# ProPrj_RP2040_SERVO_BOARD_2026-06-01.net
KiCad netlist of a schematic drawn in EasyEDA Pro
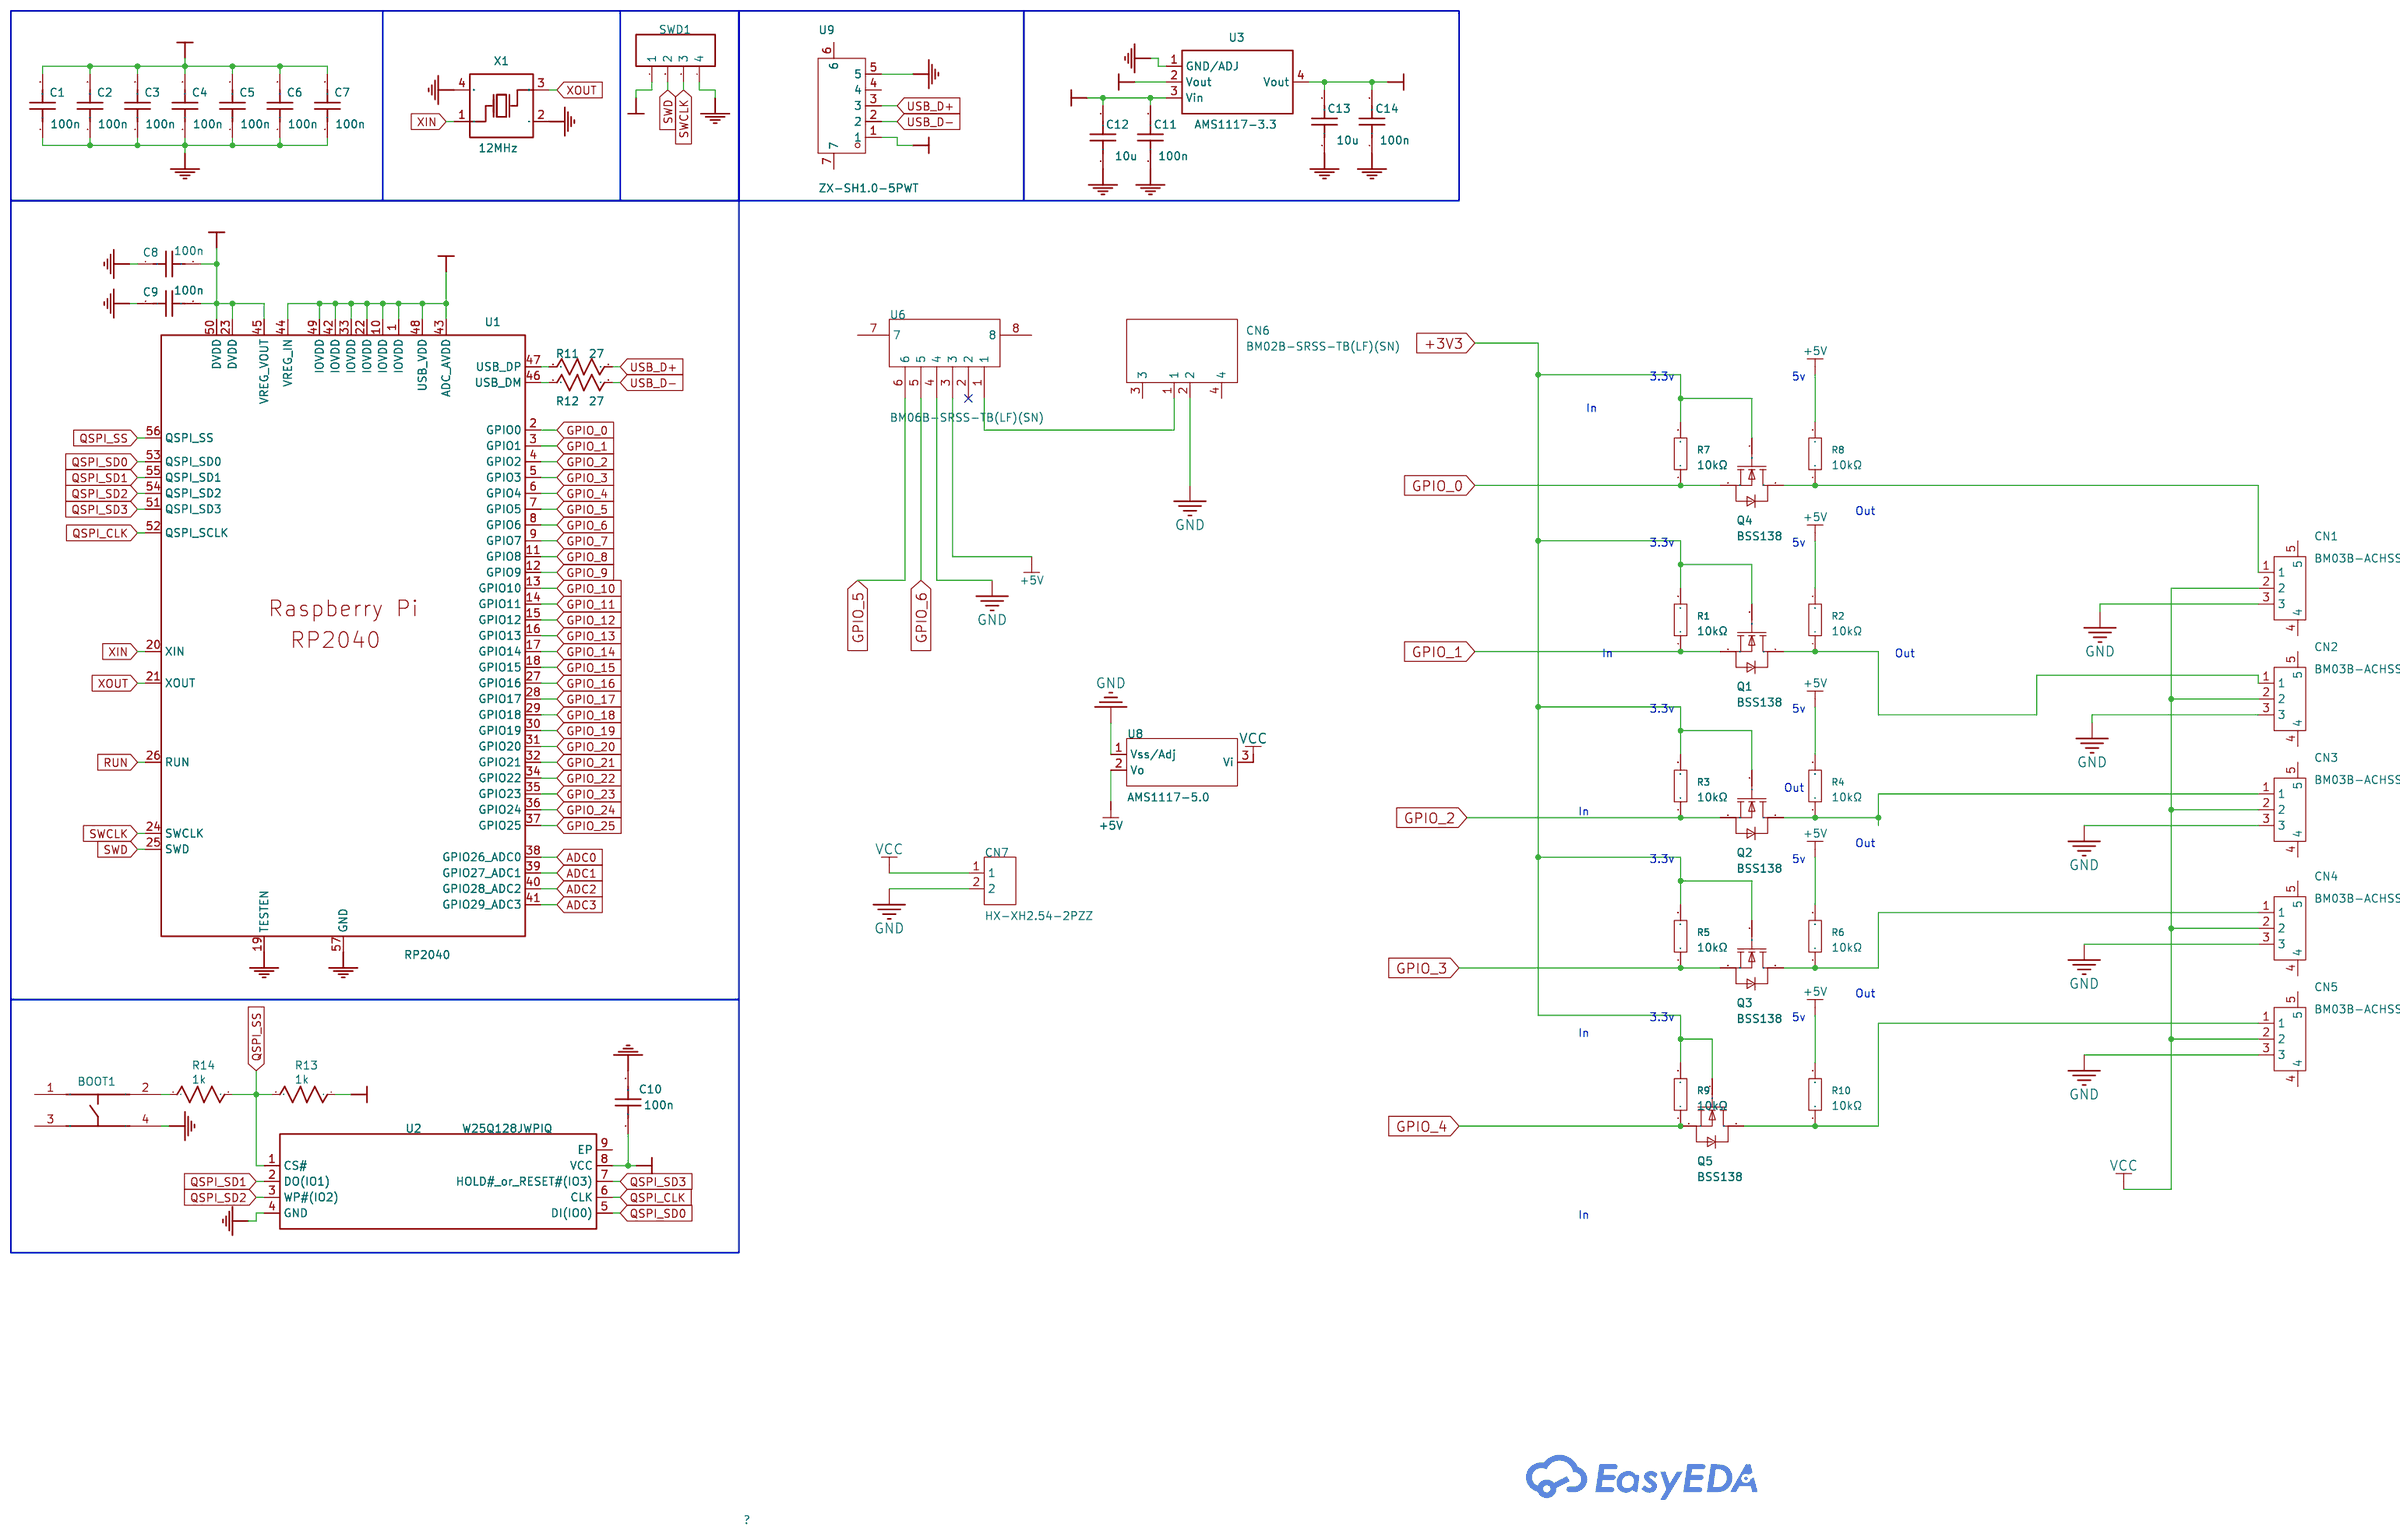
[diagram p0: schematic sheet]

(export (version "E")
  (design (tool "Eeschema 10.0.6"))
  (components
    (comp (ref "BOOT1")
      (value "PTS810SJM250SMTRLFS")
      (footprint "easyedapro:KEY-SMD_4P-L4.2-W3.2-P2.20-LS4.6")
      (fields (field (name "Manufacturer") "C&K") (field (name "Contributor") "LCSC"))
      (libsource (lib "easyedapro") (part "PTS810SJM250SMTRLFS"))
    )
    (comp (ref "C1")
      (value "100n")
      (footprint "easyedapro:C0603")
      (fields (field (name "Contributor") "LCEDA_Lib"))
      (libsource (lib "easyedapro") (part "100n"))
    )
    (comp (ref "C2")
      (value "100n")
      (footprint "easyedapro:C0603")
      (fields (field (name "Contributor") "LCEDA_Lib"))
      (libsource (lib "easyedapro") (part "100n"))
    )
    (comp (ref "C3")
      (value "100n")
      (footprint "easyedapro:C0603")
      (fields (field (name "Contributor") "LCEDA_Lib"))
      (libsource (lib "easyedapro") (part "100n"))
    )
    (comp (ref "C4")
      (value "100n")
      (footprint "easyedapro:C0603")
      (fields (field (name "Contributor") "LCEDA_Lib"))
      (libsource (lib "easyedapro") (part "100n"))
    )
    (comp (ref "C5")
      (value "100n")
      (footprint "easyedapro:C0603")
      (fields (field (name "Contributor") "LCEDA_Lib"))
      (libsource (lib "easyedapro") (part "100n"))
    )
    (comp (ref "C6")
      (value "100n")
      (footprint "easyedapro:C0603")
      (fields (field (name "Contributor") "LCEDA_Lib"))
      (libsource (lib "easyedapro") (part "100n"))
    )
    (comp (ref "C7")
      (value "100n")
      (footprint "easyedapro:C0603")
      (fields (field (name "Contributor") "LCEDA_Lib"))
      (libsource (lib "easyedapro") (part "100n"))
    )
    (comp (ref "C8")
      (value "100n")
      (footprint "easyedapro:C0603")
      (fields (field (name "Contributor") "LCEDA_Lib"))
      (libsource (lib "easyedapro") (part "100n"))
    )
    (comp (ref "C9")
      (value "100n")
      (footprint "easyedapro:C0603")
      (fields (field (name "Contributor") "LCEDA_Lib"))
      (libsource (lib "easyedapro") (part "100n"))
    )
    (comp (ref "C10")
      (value "100n")
      (footprint "easyedapro:C0603")
      (fields (field (name "Contributor") "LCEDA_Lib"))
      (libsource (lib "easyedapro") (part "100n"))
    )
    (comp (ref "C11")
      (value "100n")
      (footprint "easyedapro:C0603")
      (fields (field (name "Contributor") "LCEDA_Lib"))
      (libsource (lib "easyedapro") (part "100n"))
    )
    (comp (ref "C12")
      (value "10u")
      (footprint "easyedapro:C0603")
      (fields (field (name "Contributor") "LCEDA_Lib"))
      (libsource (lib "easyedapro") (part "10u"))
    )
    (comp (ref "C13")
      (value "10u")
      (footprint "easyedapro:C0603")
      (fields (field (name "Contributor") "LCEDA_Lib"))
      (libsource (lib "easyedapro") (part "10u"))
    )
    (comp (ref "C14")
      (value "100n")
      (footprint "easyedapro:C0603")
      (fields (field (name "Contributor") "LCEDA_Lib"))
      (libsource (lib "easyedapro") (part "100n"))
    )
    (comp (ref "CN1")
      (value "BM03B-ACHSS-GAN-TF(LF)(SN)")
      (footprint "easyedapro:CONN-SMD_3P-P1.20_BM03B-ACHSS-GAN-TF")
      (fields (field (name "Manufacturer") "JST"))
      (libsource (lib "easyedapro") (part "BM03B-ACHSS-GAN-TF(LF)(SN)"))
    )
    (comp (ref "CN2")
      (value "BM03B-ACHSS-GAN-TF(LF)(SN)")
      (footprint "easyedapro:CONN-SMD_3P-P1.20_BM03B-ACHSS-GAN-TF")
      (fields (field (name "Manufacturer") "JST"))
      (libsource (lib "easyedapro") (part "BM03B-ACHSS-GAN-TF(LF)(SN)"))
    )
    (comp (ref "CN3")
      (value "BM03B-ACHSS-GAN-TF(LF)(SN)")
      (footprint "easyedapro:CONN-SMD_3P-P1.20_BM03B-ACHSS-GAN-TF")
      (fields (field (name "Manufacturer") "JST"))
      (libsource (lib "easyedapro") (part "BM03B-ACHSS-GAN-TF(LF)(SN)"))
    )
    (comp (ref "CN4")
      (value "BM03B-ACHSS-GAN-TF(LF)(SN)")
      (footprint "easyedapro:CONN-SMD_3P-P1.20_BM03B-ACHSS-GAN-TF")
      (fields (field (name "Manufacturer") "JST"))
      (libsource (lib "easyedapro") (part "BM03B-ACHSS-GAN-TF(LF)(SN)"))
    )
    (comp (ref "CN5")
      (value "BM03B-ACHSS-GAN-TF(LF)(SN)")
      (footprint "easyedapro:CONN-SMD_3P-P1.20_BM03B-ACHSS-GAN-TF")
      (fields (field (name "Manufacturer") "JST"))
      (libsource (lib "easyedapro") (part "BM03B-ACHSS-GAN-TF(LF)(SN)"))
    )
    (comp (ref "CN6")
      (value "BM02B-SRSS-TB(LF)(SN)")
      (footprint "easyedapro:CONN-TH_BM02B-SRSS-TB-LF-SN")
      (fields (field (name "Manufacturer") "JST"))
      (libsource (lib "easyedapro") (part "BM02B-SRSS-TB (LF)(SN)"))
    )
    (comp (ref "CN7")
      (value "HX-XH2.54-2PZZ")
      (footprint "easyedapro:CONN-TH_2P-P2.50_HX-2.54MM-2P-ZZ-MS")
      (fields (field (name "Manufacturer") "hanxia(韩下)"))
      (libsource (lib "easyedapro") (part "HX-XH2.54-2PZZ"))
    )
    (comp (ref "Q1")
      (value "BSS138")
      (footprint "easyedapro:SOT-23-3_L3.0-W1.7-P0.95-LS2.9-BR")
      (fields (field (name "Manufacturer") "luJing(鲁晶)"))
      (libsource (lib "easyedapro") (part "BSS138_C53058666"))
    )
    (comp (ref "Q2")
      (value "BSS138")
      (footprint "easyedapro:SOT-23-3_L3.0-W1.7-P0.95-LS2.9-BR")
      (fields (field (name "Manufacturer") "luJing(鲁晶)"))
      (libsource (lib "easyedapro") (part "BSS138_C53058666"))
    )
    (comp (ref "Q3")
      (value "BSS138")
      (footprint "easyedapro:SOT-23-3_L3.0-W1.7-P0.95-LS2.9-BR")
      (fields (field (name "Manufacturer") "luJing(鲁晶)"))
      (libsource (lib "easyedapro") (part "BSS138_C53058666"))
    )
    (comp (ref "Q4")
      (value "BSS138")
      (footprint "easyedapro:SOT-23-3_L3.0-W1.7-P0.95-LS2.9-BR")
      (fields (field (name "Manufacturer") "luJing(鲁晶)"))
      (libsource (lib "easyedapro") (part "BSS138_C53058666"))
    )
    (comp (ref "Q5")
      (value "BSS138")
      (footprint "easyedapro:SOT-23-3_L3.0-W1.7-P0.95-LS2.9-BR")
      (fields (field (name "Manufacturer") "luJing(鲁晶)"))
      (libsource (lib "easyedapro") (part "BSS138_C53058666"))
    )
    (comp (ref "R1")
      (value "10kΩ")
      (footprint "easyedapro:R0402")
      (fields
        (field (name "Manufacturer Part") "TR0402D10K0Q1025Z")
        (field (name "Manufacturer") "EVER OHMS(天二科技)")
      )
      (libsource (lib "easyedapro") (part "TR0402D10KQ1025"))
    )
    (comp (ref "R2")
      (value "10kΩ")
      (footprint "easyedapro:R0402")
      (fields
        (field (name "Manufacturer Part") "TR0402D10K0Q1025Z")
        (field (name "Manufacturer") "EVER OHMS(天二科技)")
      )
      (libsource (lib "easyedapro") (part "TR0402D10KQ1025"))
    )
    (comp (ref "R3")
      (value "10kΩ")
      (footprint "easyedapro:R0402")
      (fields
        (field (name "Manufacturer Part") "TR0402D10K0Q1025Z")
        (field (name "Manufacturer") "EVER OHMS(天二科技)")
      )
      (libsource (lib "easyedapro") (part "TR0402D10KQ1025"))
    )
    (comp (ref "R4")
      (value "10kΩ")
      (footprint "easyedapro:R0402")
      (fields
        (field (name "Manufacturer Part") "TR0402D10K0Q1025Z")
        (field (name "Manufacturer") "EVER OHMS(天二科技)")
      )
      (libsource (lib "easyedapro") (part "TR0402D10KQ1025"))
    )
    (comp (ref "R5")
      (value "10kΩ")
      (footprint "easyedapro:R0402")
      (fields
        (field (name "Manufacturer Part") "TR0402D10K0Q1025Z")
        (field (name "Manufacturer") "EVER OHMS(天二科技)")
      )
      (libsource (lib "easyedapro") (part "TR0402D10KQ1025"))
    )
    (comp (ref "R6")
      (value "10kΩ")
      (footprint "easyedapro:R0402")
      (fields
        (field (name "Manufacturer Part") "TR0402D10K0Q1025Z")
        (field (name "Manufacturer") "EVER OHMS(天二科技)")
      )
      (libsource (lib "easyedapro") (part "TR0402D10KQ1025"))
    )
    (comp (ref "R7")
      (value "10kΩ")
      (footprint "easyedapro:R0402")
      (fields
        (field (name "Manufacturer Part") "TR0402D10K0Q1025Z")
        (field (name "Manufacturer") "EVER OHMS(天二科技)")
      )
      (libsource (lib "easyedapro") (part "TR0402D10KQ1025"))
    )
    (comp (ref "R8")
      (value "10kΩ")
      (footprint "easyedapro:R0402")
      (fields
        (field (name "Manufacturer Part") "TR0402D10K0Q1025Z")
        (field (name "Manufacturer") "EVER OHMS(天二科技)")
      )
      (libsource (lib "easyedapro") (part "TR0402D10KQ1025"))
    )
    (comp (ref "R9")
      (value "10kΩ")
      (footprint "easyedapro:R0402")
      (fields
        (field (name "Manufacturer Part") "TR0402D10K0Q1025Z")
        (field (name "Manufacturer") "EVER OHMS(天二科技)")
      )
      (libsource (lib "easyedapro") (part "TR0402D10KQ1025"))
    )
    (comp (ref "R10")
      (value "10kΩ")
      (footprint "easyedapro:R0402")
      (fields
        (field (name "Manufacturer Part") "TR0402D10K0Q1025Z")
        (field (name "Manufacturer") "EVER OHMS(天二科技)")
      )
      (libsource (lib "easyedapro") (part "TR0402D10KQ1025"))
    )
    (comp (ref "R11")
      (value "27")
      (footprint "easyedapro:R0603")
      (fields (field (name "Contributor") "LCEDA_Lib"))
      (libsource (lib "easyedapro") (part "27"))
    )
    (comp (ref "R12")
      (value "27")
      (footprint "easyedapro:R0603")
      (fields (field (name "Contributor") "LCEDA_Lib"))
      (libsource (lib "easyedapro") (part "27"))
    )
    (comp (ref "R13")
      (value "1k")
      (footprint "easyedapro:R0603")
      (fields (field (name "Contributor") "LCEDA_Lib"))
      (libsource (lib "easyedapro") (part "1k"))
    )
    (comp (ref "R14")
      (value "1k")
      (footprint "easyedapro:R0603")
      (fields (field (name "Contributor") "LCEDA_Lib"))
      (libsource (lib "easyedapro") (part "1k"))
    )
    (comp (ref "SWD1")
      (value "HDR-M-2.54_1x4")
      (footprint "easyedapro:HDR-M-2.54_1X4")
      (fields (field (name "Contributor") "LCEDA_Lib"))
      (libsource (lib "easyedapro") (part "HDR-M-2.54_1x4"))
    )
    (comp (ref "U1")
      (value "RP2040")
      (footprint "easyedapro:LQFN-56_L7.0-W7.0-P0.4-EP")
      (fields (field (name "Manufacturer") "Raspberry Pi(树莓派)") (field (name "Contributor") "LCSC"))
      (libsource (lib "easyedapro") (part "RP2040"))
    )
    (comp (ref "U2")
      (value "W25Q128JWPIQ")
      (footprint "easyedapro:WSON-8_L6.0-W5.0-P1.27-BL-EP")
      (fields (field (name "Manufacturer") "WINBOND(华邦)") (field (name "Contributor") "LCSC"))
      (libsource (lib "easyedapro") (part "W25Q128JWPIQ"))
    )
    (comp (ref "U3")
      (value "AMS1117-3.3")
      (footprint "easyedapro:SOT-223-3_L6.5-W3.4-P2.30-LS7.0-BR")
      (fields (field (name "Manufacturer") "AMS"))
      (libsource (lib "easyedapro") (part "AMS1117-3.3"))
    )
    (comp (ref "U6")
      (value "BM06B-SRSS-TB(LF)(SN)")
      (footprint "easyedapro:CONN-SMD-6P-P1.00_BM06B-SRSS-TB-LF-SN")
      (fields (field (name "Manufacturer") "JST"))
      (libsource (lib "easyedapro") (part "BM06B-SRSS-TB(LF)(SN)"))
    )
    (comp (ref "U8")
      (value "AMS1117-5.0")
      (footprint "easyedapro:SOT-89-3_L4.5-W2.5-P1.50-LS4.0-BR-1")
      (fields (field (name "Manufacturer") "FOSAN(富捷/富信)"))
      (libsource (lib "easyedapro") (part "AMS1117-5.0_C42410722"))
    )
    (comp (ref "U9")
      (value "ZX-SH1.0-5PWT")
      (footprint "easyedapro:CONN-SMD_5P-P1.00_MEGASTAR_ZX-SH1.0-5PWT")
      (fields (field (name "Manufacturer") "Megastar(兆星)"))
      (libsource (lib "easyedapro") (part "ZX-SH1.0-5PWT"))
    )
    (comp (ref "X1")
      (value "12MHz")
      (footprint "easyedapro:CRYSTAL-SMD_4P-L3.2-W2.5-BL")
      (fields
        (field (name "Manufacturer Part") "SMD-3225_4P12M12pf10ppm")
        (field (name "Manufacturer") "TAE")
        (field (name "Contributor") "LCSC")
      )
      (libsource (lib "easyedapro") (part "12MHz"))
    )
  )
  (nets
    (net (code "1") (name "+1V1") (class "Default")
      (node (ref "C8") (pin "2") (pinfunction "2_2") (pintype "unspecified"))
      (node (ref "C9") (pin "2") (pinfunction "2_2") (pintype "unspecified"))
      (node (ref "U1") (pin "23") (pinfunction "DVDD_23") (pintype "bidirectional"))
      (node (ref "U1") (pin "45") (pinfunction "VREG_VOUT_45") (pintype "bidirectional"))
      (node (ref "U1") (pin "50") (pinfunction "DVDD_50") (pintype "bidirectional"))
    )
    (net (code "2") (name "+3.3V") (class "Default")
      (node (ref "U1") (pin "1") (pinfunction "IOVDD_1") (pintype "bidirectional"))
      (node (ref "U1") (pin "10") (pinfunction "IOVDD_10") (pintype "bidirectional"))
      (node (ref "U1") (pin "22") (pinfunction "IOVDD_22") (pintype "bidirectional"))
      (node (ref "U1") (pin "33") (pinfunction "IOVDD_33") (pintype "bidirectional"))
      (node (ref "U1") (pin "42") (pinfunction "IOVDD_42") (pintype "bidirectional"))
      (node (ref "U1") (pin "43") (pinfunction "ADC_AVDD_43") (pintype "bidirectional"))
      (node (ref "U1") (pin "44") (pinfunction "VREG_IN_44") (pintype "bidirectional"))
      (node (ref "U1") (pin "48") (pinfunction "USB_VDD_48") (pintype "bidirectional"))
      (node (ref "U1") (pin "49") (pinfunction "IOVDD_49") (pintype "bidirectional"))
    )
    (net (code "3") (name "+3V3") (class "Default")
      (node (ref "C1") (pin "2") (pinfunction "2_2") (pintype "unspecified"))
      (node (ref "C10") (pin "1") (pinfunction "1_1") (pintype "unspecified"))
      (node (ref "C13") (pin "2") (pinfunction "2_2") (pintype "unspecified"))
      (node (ref "C14") (pin "2") (pinfunction "2_2") (pintype "unspecified"))
      (node (ref "C2") (pin "2") (pinfunction "2_2") (pintype "unspecified"))
      (node (ref "C3") (pin "2") (pinfunction "2_2") (pintype "unspecified"))
      (node (ref "C4") (pin "2") (pinfunction "2_2") (pintype "unspecified"))
      (node (ref "C5") (pin "2") (pinfunction "2_2") (pintype "unspecified"))
      (node (ref "C6") (pin "2") (pinfunction "2_2") (pintype "unspecified"))
      (node (ref "C7") (pin "2") (pinfunction "2_2") (pintype "unspecified"))
      (node (ref "Q1") (pin "1") (pinfunction "G_1") (pintype "unspecified"))
      (node (ref "Q2") (pin "1") (pinfunction "G_1") (pintype "unspecified"))
      (node (ref "Q3") (pin "1") (pinfunction "G_1") (pintype "unspecified"))
      (node (ref "Q4") (pin "1") (pinfunction "G_1") (pintype "unspecified"))
      (node (ref "Q5") (pin "1") (pinfunction "G_1") (pintype "unspecified"))
      (node (ref "R1") (pin "2") (pinfunction "2_2") (pintype "input"))
      (node (ref "R13") (pin "1") (pinfunction "1_1") (pintype "unspecified"))
      (node (ref "R3") (pin "2") (pinfunction "2_2") (pintype "input"))
      (node (ref "R5") (pin "2") (pinfunction "2_2") (pintype "input"))
      (node (ref "R7") (pin "2") (pinfunction "2_2") (pintype "input"))
      (node (ref "R9") (pin "2") (pinfunction "2_2") (pintype "input"))
      (node (ref "SWD1") (pin "1") (pinfunction "1_1") (pintype "unspecified"))
      (node (ref "U2") (pin "8") (pinfunction "VCC_8") (pintype "unspecified"))
      (node (ref "U3") (pin "2") (pinfunction "Vout_2") (pintype "unspecified"))
      (node (ref "U3") (pin "4") (pinfunction "Vout_4") (pintype "unspecified"))
    )
    (net (code "4") (name "+5V") (class "Default")
      (node (ref "C11") (pin "2") (pinfunction "2_2") (pintype "unspecified"))
      (node (ref "C12") (pin "2") (pinfunction "2_2") (pintype "unspecified"))
      (node (ref "R10") (pin "2") (pinfunction "2_2") (pintype "input"))
      (node (ref "R2") (pin "2") (pinfunction "2_2") (pintype "input"))
      (node (ref "R4") (pin "2") (pinfunction "2_2") (pintype "input"))
      (node (ref "R6") (pin "2") (pinfunction "2_2") (pintype "input"))
      (node (ref "R8") (pin "2") (pinfunction "2_2") (pintype "input"))
      (node (ref "U3") (pin "3") (pinfunction "Vin_3") (pintype "unspecified"))
      (node (ref "U6") (pin "3") (pinfunction "3_3") (pintype "unspecified"))
      (node (ref "U8") (pin "2") (pinfunction "Vo_2") (pintype "unspecified"))
      (node (ref "U9") (pin "1") (pinfunction "1_1") (pintype "unspecified"))
    )
    (net (code "5") (name "ADC0") (class "Default")
      (node (ref "U1") (pin "38") (pinfunction "GPIO26_ADC0_38") (pintype "bidirectional"))
    )
    (net (code "6") (name "ADC1") (class "Default")
      (node (ref "U1") (pin "39") (pinfunction "GPIO27_ADC1_39") (pintype "bidirectional"))
    )
    (net (code "7") (name "ADC2") (class "Default")
      (node (ref "U1") (pin "40") (pinfunction "GPIO28_ADC2_40") (pintype "bidirectional"))
    )
    (net (code "8") (name "ADC3") (class "Default")
      (node (ref "U1") (pin "41") (pinfunction "GPIO29_ADC3_41") (pintype "bidirectional"))
    )
    (net (code "9") (name "GND") (class "Default")
      (node (ref "BOOT1") (pin "4") (pinfunction "4_4") (pintype "unspecified"))
      (node (ref "C1") (pin "1") (pinfunction "1_1") (pintype "unspecified"))
      (node (ref "C10") (pin "2") (pinfunction "2_2") (pintype "unspecified"))
      (node (ref "C11") (pin "1") (pinfunction "1_1") (pintype "unspecified"))
      (node (ref "C12") (pin "1") (pinfunction "1_1") (pintype "unspecified"))
      (node (ref "C13") (pin "1") (pinfunction "1_1") (pintype "unspecified"))
      (node (ref "C14") (pin "1") (pinfunction "1_1") (pintype "unspecified"))
      (node (ref "C2") (pin "1") (pinfunction "1_1") (pintype "unspecified"))
      (node (ref "C3") (pin "1") (pinfunction "1_1") (pintype "unspecified"))
      (node (ref "C4") (pin "1") (pinfunction "1_1") (pintype "unspecified"))
      (node (ref "C5") (pin "1") (pinfunction "1_1") (pintype "unspecified"))
      (node (ref "C6") (pin "1") (pinfunction "1_1") (pintype "unspecified"))
      (node (ref "C7") (pin "1") (pinfunction "1_1") (pintype "unspecified"))
      (node (ref "C8") (pin "1") (pinfunction "1_1") (pintype "unspecified"))
      (node (ref "C9") (pin "1") (pinfunction "1_1") (pintype "unspecified"))
      (node (ref "CN1") (pin "3") (pinfunction "3_3") (pintype "unspecified"))
      (node (ref "CN2") (pin "3") (pinfunction "3_3") (pintype "unspecified"))
      (node (ref "CN3") (pin "3") (pinfunction "3_3") (pintype "unspecified"))
      (node (ref "CN4") (pin "3") (pinfunction "3_3") (pintype "unspecified"))
      (node (ref "CN5") (pin "3") (pinfunction "3_3") (pintype "unspecified"))
      (node (ref "CN6") (pin "2") (pinfunction "2_2") (pintype "unspecified"))
      (node (ref "CN7") (pin "2") (pinfunction "2_2") (pintype "unspecified"))
      (node (ref "SWD1") (pin "4") (pinfunction "4_4") (pintype "unspecified"))
      (node (ref "U1") (pin "19") (pinfunction "TESTEN_19") (pintype "unspecified"))
      (node (ref "U1") (pin "57") (pinfunction "GND_57") (pintype "bidirectional"))
      (node (ref "U2") (pin "4") (pinfunction "GND_4") (pintype "unspecified"))
      (node (ref "U3") (pin "1") (pinfunction "GND/ADJ_1") (pintype "unspecified"))
      (node (ref "U6") (pin "4") (pinfunction "4_4") (pintype "unspecified"))
      (node (ref "U8") (pin "1") (pinfunction "Vss/Adj_1") (pintype "unspecified"))
      (node (ref "U9") (pin "5") (pinfunction "5_5") (pintype "unspecified"))
      (node (ref "X1") (pin "2") (pinfunction "GND_2") (pintype "unspecified"))
      (node (ref "X1") (pin "4") (pinfunction "GND_4") (pintype "unspecified"))
    )
    (net (code "10") (name "GPIO_0") (class "Default")
      (node (ref "Q4") (pin "2") (pinfunction "S_2") (pintype "unspecified"))
      (node (ref "R7") (pin "1") (pinfunction "1_1") (pintype "input"))
      (node (ref "U1") (pin "2") (pinfunction "GPIO0_2") (pintype "bidirectional"))
    )
    (net (code "11") (name "GPIO_1") (class "Default")
      (node (ref "Q1") (pin "2") (pinfunction "S_2") (pintype "unspecified"))
      (node (ref "R1") (pin "1") (pinfunction "1_1") (pintype "input"))
      (node (ref "U1") (pin "3") (pinfunction "GPIO1_3") (pintype "bidirectional"))
    )
    (net (code "12") (name "GPIO_2") (class "Default")
      (node (ref "Q2") (pin "2") (pinfunction "S_2") (pintype "unspecified"))
      (node (ref "R3") (pin "1") (pinfunction "1_1") (pintype "input"))
      (node (ref "U1") (pin "4") (pinfunction "GPIO2_4") (pintype "bidirectional"))
    )
    (net (code "13") (name "GPIO_3") (class "Default")
      (node (ref "Q3") (pin "2") (pinfunction "S_2") (pintype "unspecified"))
      (node (ref "R5") (pin "1") (pinfunction "1_1") (pintype "input"))
      (node (ref "U1") (pin "5") (pinfunction "GPIO3_5") (pintype "bidirectional"))
    )
    (net (code "14") (name "GPIO_4") (class "Default")
      (node (ref "Q5") (pin "2") (pinfunction "S_2") (pintype "unspecified"))
      (node (ref "R9") (pin "1") (pinfunction "1_1") (pintype "input"))
      (node (ref "U1") (pin "6") (pinfunction "GPIO4_6") (pintype "bidirectional"))
    )
    (net (code "15") (name "GPIO_5") (class "Default")
      (node (ref "U1") (pin "7") (pinfunction "GPIO5_7") (pintype "bidirectional"))
      (node (ref "U6") (pin "6") (pinfunction "6_6") (pintype "unspecified"))
    )
    (net (code "16") (name "GPIO_6") (class "Default")
      (node (ref "U1") (pin "8") (pinfunction "GPIO6_8") (pintype "bidirectional"))
      (node (ref "U6") (pin "5") (pinfunction "5_5") (pintype "unspecified"))
    )
    (net (code "17") (name "GPIO_7") (class "Default")
      (node (ref "U1") (pin "9") (pinfunction "GPIO7_9") (pintype "bidirectional"))
    )
    (net (code "18") (name "GPIO_8") (class "Default")
      (node (ref "U1") (pin "11") (pinfunction "GPIO8_11") (pintype "bidirectional"))
    )
    (net (code "19") (name "GPIO_9") (class "Default")
      (node (ref "U1") (pin "12") (pinfunction "GPIO9_12") (pintype "bidirectional"))
    )
    (net (code "20") (name "GPIO_10") (class "Default")
      (node (ref "U1") (pin "13") (pinfunction "GPIO10_13") (pintype "bidirectional"))
    )
    (net (code "21") (name "GPIO_11") (class "Default")
      (node (ref "U1") (pin "14") (pinfunction "GPIO11_14") (pintype "bidirectional"))
    )
    (net (code "22") (name "GPIO_12") (class "Default")
      (node (ref "U1") (pin "15") (pinfunction "GPIO12_15") (pintype "bidirectional"))
    )
    (net (code "23") (name "GPIO_13") (class "Default")
      (node (ref "U1") (pin "16") (pinfunction "GPIO13_16") (pintype "bidirectional"))
    )
    (net (code "24") (name "GPIO_14") (class "Default")
      (node (ref "U1") (pin "17") (pinfunction "GPIO14_17") (pintype "bidirectional"))
    )
    (net (code "25") (name "GPIO_15") (class "Default")
      (node (ref "U1") (pin "18") (pinfunction "GPIO15_18") (pintype "bidirectional"))
    )
    (net (code "26") (name "GPIO_16") (class "Default")
      (node (ref "U1") (pin "27") (pinfunction "GPIO16_27") (pintype "bidirectional"))
    )
    (net (code "27") (name "GPIO_17") (class "Default")
      (node (ref "U1") (pin "28") (pinfunction "GPIO17_28") (pintype "bidirectional"))
    )
    (net (code "28") (name "GPIO_18") (class "Default")
      (node (ref "U1") (pin "29") (pinfunction "GPIO18_29") (pintype "bidirectional"))
    )
    (net (code "29") (name "GPIO_19") (class "Default")
      (node (ref "U1") (pin "30") (pinfunction "GPIO19_30") (pintype "bidirectional"))
    )
    (net (code "30") (name "GPIO_20") (class "Default")
      (node (ref "U1") (pin "31") (pinfunction "GPIO20_31") (pintype "bidirectional"))
    )
    (net (code "31") (name "GPIO_21") (class "Default")
      (node (ref "U1") (pin "32") (pinfunction "GPIO21_32") (pintype "bidirectional"))
    )
    (net (code "32") (name "GPIO_22") (class "Default")
      (node (ref "U1") (pin "34") (pinfunction "GPIO22_34") (pintype "bidirectional"))
    )
    (net (code "33") (name "GPIO_23") (class "Default")
      (node (ref "U1") (pin "35") (pinfunction "GPIO23_35") (pintype "bidirectional"))
    )
    (net (code "34") (name "GPIO_24") (class "Default")
      (node (ref "U1") (pin "36") (pinfunction "GPIO24_36") (pintype "bidirectional"))
    )
    (net (code "35") (name "GPIO_25") (class "Default")
      (node (ref "U1") (pin "37") (pinfunction "GPIO25_37") (pintype "bidirectional"))
    )
    (net (code "36") (name "Net-(BOOT1-Pad2)") (class "Default")
      (node (ref "BOOT1") (pin "2") (pinfunction "2_2") (pintype "unspecified"))
      (node (ref "R14") (pin "1") (pinfunction "1_1") (pintype "unspecified"))
    )
    (net (code "37") (name "Net-(CN6-Pad1)") (class "Default")
      (node (ref "CN6") (pin "1") (pinfunction "1_1") (pintype "unspecified"))
      (node (ref "U6") (pin "1") (pinfunction "1_1") (pintype "unspecified"))
    )
    (net (code "38") (name "Net-(Q1-D)") (class "Default")
      (node (ref "CN2") (pin "1") (pinfunction "1_1") (pintype "unspecified"))
      (node (ref "Q1") (pin "3") (pinfunction "D_3") (pintype "unspecified"))
      (node (ref "R2") (pin "1") (pinfunction "1_1") (pintype "input"))
    )
    (net (code "39") (name "Net-(Q2-D)") (class "Default")
      (node (ref "CN3") (pin "1") (pinfunction "1_1") (pintype "unspecified"))
      (node (ref "Q2") (pin "3") (pinfunction "D_3") (pintype "unspecified"))
      (node (ref "R4") (pin "1") (pinfunction "1_1") (pintype "input"))
    )
    (net (code "40") (name "Net-(Q3-D)") (class "Default")
      (node (ref "CN4") (pin "1") (pinfunction "1_1") (pintype "unspecified"))
      (node (ref "Q3") (pin "3") (pinfunction "D_3") (pintype "unspecified"))
      (node (ref "R6") (pin "1") (pinfunction "1_1") (pintype "input"))
    )
    (net (code "41") (name "Net-(Q4-D)") (class "Default")
      (node (ref "CN1") (pin "1") (pinfunction "1_1") (pintype "unspecified"))
      (node (ref "Q4") (pin "3") (pinfunction "D_3") (pintype "unspecified"))
      (node (ref "R8") (pin "1") (pinfunction "1_1") (pintype "input"))
    )
    (net (code "42") (name "Net-(Q5-D)") (class "Default")
      (node (ref "CN5") (pin "1") (pinfunction "1_1") (pintype "unspecified"))
      (node (ref "Q5") (pin "3") (pinfunction "D_3") (pintype "unspecified"))
      (node (ref "R10") (pin "1") (pinfunction "1_1") (pintype "input"))
    )
    (net (code "43") (name "Net-(U1-USB_DM)") (class "Default")
      (node (ref "R12") (pin "1") (pinfunction "1_1") (pintype "unspecified"))
      (node (ref "U1") (pin "46") (pinfunction "USB_DM_46") (pintype "bidirectional"))
    )
    (net (code "44") (name "Net-(U1-USB_DP)") (class "Default")
      (node (ref "R11") (pin "1") (pinfunction "1_1") (pintype "unspecified"))
      (node (ref "U1") (pin "47") (pinfunction "USB_DP_47") (pintype "bidirectional"))
    )
    (net (code "45") (name "QSPI_CLK") (class "Default")
      (node (ref "U1") (pin "52") (pinfunction "QSPI_SCLK_52") (pintype "output"))
      (node (ref "U2") (pin "6") (pinfunction "CLK_6") (pintype "unspecified"))
    )
    (net (code "46") (name "QSPI_SD0") (class "Default")
      (node (ref "U1") (pin "53") (pinfunction "QSPI_SD0_53") (pintype "bidirectional"))
      (node (ref "U2") (pin "5") (pinfunction "DI(IO0)_5") (pintype "unspecified"))
    )
    (net (code "47") (name "QSPI_SD1") (class "Default")
      (node (ref "U1") (pin "55") (pinfunction "QSPI_SD1_55") (pintype "bidirectional"))
      (node (ref "U2") (pin "2") (pinfunction "DO(IO1)_2") (pintype "unspecified"))
    )
    (net (code "48") (name "QSPI_SD2") (class "Default")
      (node (ref "U1") (pin "54") (pinfunction "QSPI_SD2_54") (pintype "bidirectional"))
      (node (ref "U2") (pin "3") (pinfunction "WP#(IO2)_3") (pintype "unspecified"))
    )
    (net (code "49") (name "QSPI_SD3") (class "Default")
      (node (ref "U1") (pin "51") (pinfunction "QSPI_SD3_51") (pintype "bidirectional"))
      (node (ref "U2") (pin "7") (pinfunction "HOLD#_or_RESET#(IO3)_7") (pintype "unspecified"))
    )
    (net (code "50") (name "QSPI_SS") (class "Default")
      (node (ref "R13") (pin "2") (pinfunction "2_2") (pintype "unspecified"))
      (node (ref "R14") (pin "2") (pinfunction "2_2") (pintype "unspecified"))
      (node (ref "U1") (pin "56") (pinfunction "QSPI_SS_56") (pintype "bidirectional"))
      (node (ref "U2") (pin "1") (pinfunction "CS#_1") (pintype "unspecified"))
    )
    (net (code "51") (name "RUN") (class "Default")
      (node (ref "U1") (pin "26") (pinfunction "RUN_26") (pintype "input"))
    )
    (net (code "52") (name "SWCLK") (class "Default")
      (node (ref "SWD1") (pin "3") (pinfunction "3_3") (pintype "unspecified"))
      (node (ref "U1") (pin "24") (pinfunction "SWCLK_24") (pintype "output"))
    )
    (net (code "53") (name "SWD") (class "Default")
      (node (ref "SWD1") (pin "2") (pinfunction "2_2") (pintype "unspecified"))
      (node (ref "U1") (pin "25") (pinfunction "SWD_25") (pintype "bidirectional"))
    )
    (net (code "54") (name "USB_D+") (class "Default")
      (node (ref "R11") (pin "2") (pinfunction "2_2") (pintype "unspecified"))
      (node (ref "U9") (pin "3") (pinfunction "3_3") (pintype "unspecified"))
    )
    (net (code "55") (name "USB_D-") (class "Default")
      (node (ref "R12") (pin "2") (pinfunction "2_2") (pintype "unspecified"))
      (node (ref "U9") (pin "2") (pinfunction "2_2") (pintype "unspecified"))
    )
    (net (code "56") (name "VCC") (class "Default")
      (node (ref "CN1") (pin "2") (pinfunction "2_2") (pintype "unspecified"))
      (node (ref "CN2") (pin "2") (pinfunction "2_2") (pintype "unspecified"))
      (node (ref "CN3") (pin "2") (pinfunction "2_2") (pintype "unspecified"))
      (node (ref "CN4") (pin "2") (pinfunction "2_2") (pintype "unspecified"))
      (node (ref "CN5") (pin "2") (pinfunction "2_2") (pintype "unspecified"))
      (node (ref "CN7") (pin "1") (pinfunction "1_1") (pintype "unspecified"))
      (node (ref "U8") (pin "3") (pinfunction "Vi_3") (pintype "unspecified"))
    )
    (net (code "57") (name "XIN") (class "Default")
      (node (ref "U1") (pin "20") (pinfunction "XIN_20") (pintype "input"))
      (node (ref "X1") (pin "1") (pinfunction "OSC1_1") (pintype "unspecified"))
    )
    (net (code "58") (name "XOUT") (class "Default")
      (node (ref "U1") (pin "21") (pinfunction "XOUT_21") (pintype "unspecified"))
      (node (ref "X1") (pin "3") (pinfunction "OSC2_3") (pintype "unspecified"))
    )
    (net (code "59") (name "unconnected-(BOOT1-Pad1)") (class "Default")
      (node (ref "BOOT1") (pin "1") (pinfunction "1_1") (pintype "unspecified"))
    )
    (net (code "60") (name "unconnected-(BOOT1-Pad3)") (class "Default")
      (node (ref "BOOT1") (pin "3") (pinfunction "3_3") (pintype "unspecified"))
    )
    (net (code "61") (name "unconnected-(CN1-Pad4)") (class "Default")
      (node (ref "CN1") (pin "4") (pinfunction "4_4") (pintype "unspecified"))
    )
    (net (code "62") (name "unconnected-(CN1-Pad5)") (class "Default")
      (node (ref "CN1") (pin "5") (pinfunction "5_5") (pintype "unspecified"))
    )
    (net (code "63") (name "unconnected-(CN2-Pad4)") (class "Default")
      (node (ref "CN2") (pin "4") (pinfunction "4_4") (pintype "unspecified"))
    )
    (net (code "64") (name "unconnected-(CN2-Pad5)") (class "Default")
      (node (ref "CN2") (pin "5") (pinfunction "5_5") (pintype "unspecified"))
    )
    (net (code "65") (name "unconnected-(CN3-Pad4)") (class "Default")
      (node (ref "CN3") (pin "4") (pinfunction "4_4") (pintype "unspecified"))
    )
    (net (code "66") (name "unconnected-(CN3-Pad5)") (class "Default")
      (node (ref "CN3") (pin "5") (pinfunction "5_5") (pintype "unspecified"))
    )
    (net (code "67") (name "unconnected-(CN4-Pad4)") (class "Default")
      (node (ref "CN4") (pin "4") (pinfunction "4_4") (pintype "unspecified"))
    )
    (net (code "68") (name "unconnected-(CN4-Pad5)") (class "Default")
      (node (ref "CN4") (pin "5") (pinfunction "5_5") (pintype "unspecified"))
    )
    (net (code "69") (name "unconnected-(CN5-Pad4)") (class "Default")
      (node (ref "CN5") (pin "4") (pinfunction "4_4") (pintype "unspecified"))
    )
    (net (code "70") (name "unconnected-(CN5-Pad5)") (class "Default")
      (node (ref "CN5") (pin "5") (pinfunction "5_5") (pintype "unspecified"))
    )
    (net (code "71") (name "unconnected-(CN6-Pad3)") (class "Default")
      (node (ref "CN6") (pin "3") (pinfunction "3_3") (pintype "unspecified"))
    )
    (net (code "72") (name "unconnected-(CN6-Pad4)") (class "Default")
      (node (ref "CN6") (pin "4") (pinfunction "4_4") (pintype "unspecified"))
    )
    (net (code "73") (name "unconnected-(U2-EP-Pad9)") (class "Default")
      (node (ref "U2") (pin "9") (pinfunction "EP_9") (pintype "unspecified"))
    )
    (net (code "74") (name "unconnected-(U6-Pad2)") (class "Default")
      (node (ref "U6") (pin "2") (pinfunction "2_2") (pintype "unspecified+no_connect"))
    )
    (net (code "75") (name "unconnected-(U6-Pad7)") (class "Default")
      (node (ref "U6") (pin "7") (pinfunction "7_7") (pintype "unspecified"))
    )
    (net (code "76") (name "unconnected-(U6-Pad8)") (class "Default")
      (node (ref "U6") (pin "8") (pinfunction "8_8") (pintype "unspecified"))
    )
    (net (code "77") (name "unconnected-(U9-Pad4)") (class "Default")
      (node (ref "U9") (pin "4") (pinfunction "4_4") (pintype "unspecified"))
    )
    (net (code "78") (name "unconnected-(U9-Pad6)") (class "Default")
      (node (ref "U9") (pin "6") (pinfunction "6_6") (pintype "unspecified"))
    )
    (net (code "79") (name "unconnected-(U9-Pad7)") (class "Default")
      (node (ref "U9") (pin "7") (pinfunction "7_7") (pintype "unspecified"))
    )
  )
)
